# DOut.net
KiCad netlist of a schematic drawn in Altium Designer
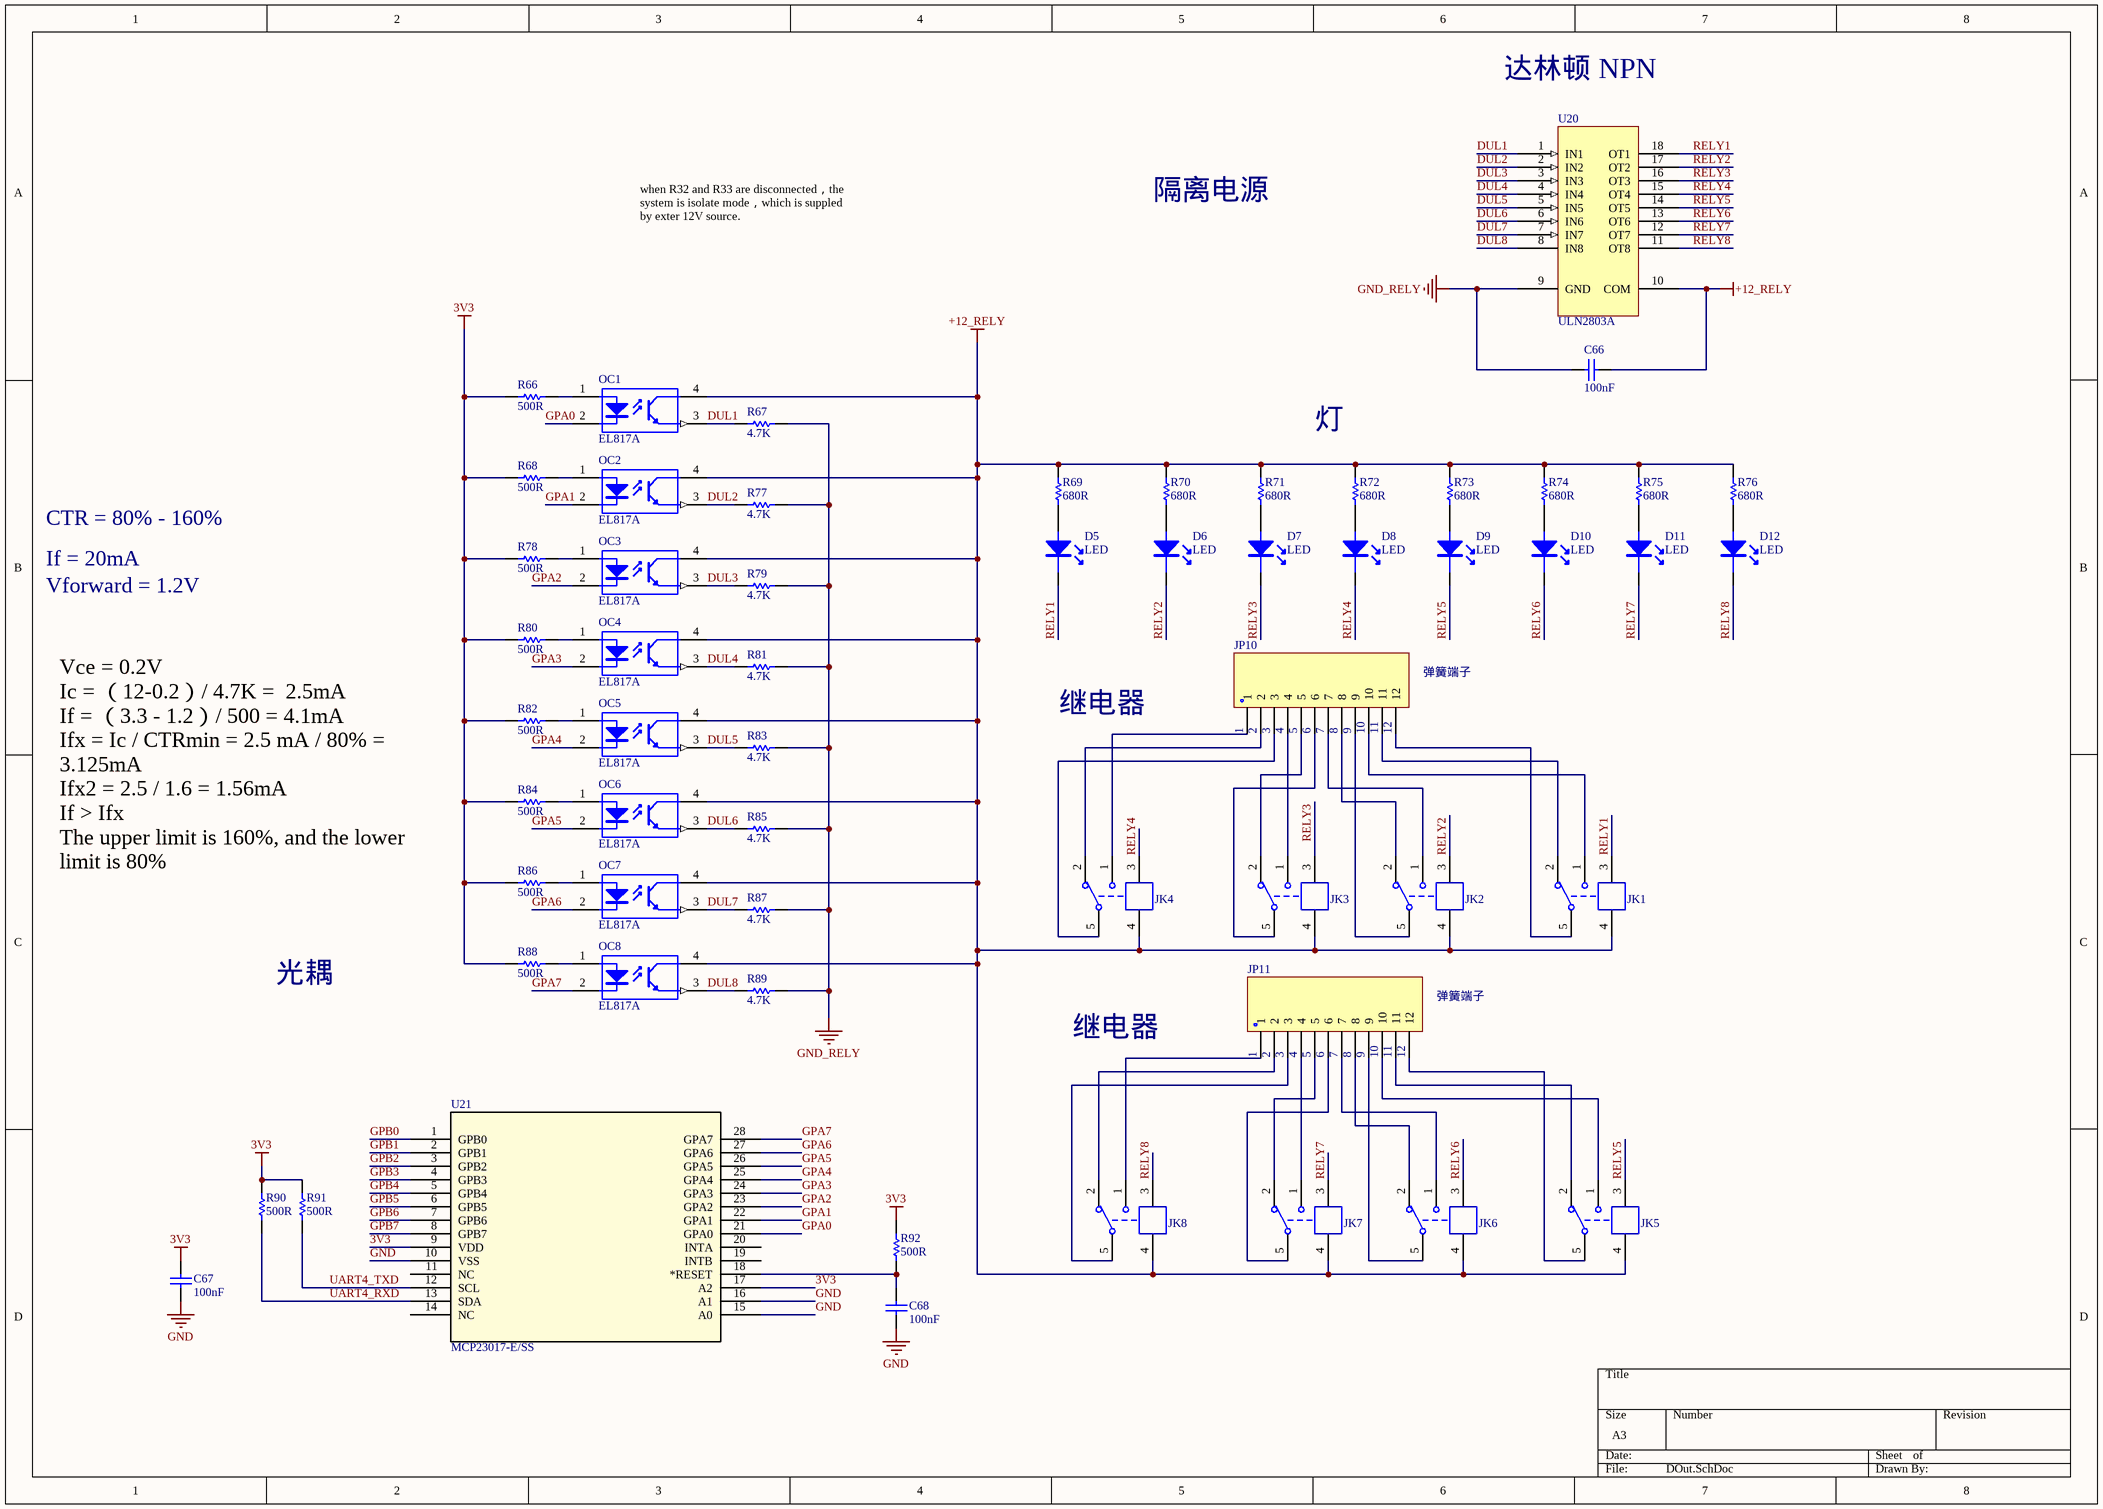
[diagram p0: DOut.SchDoc]

(export (version "E")
  (design (tool "Eeschema 10.0.6"))
  (components
    (comp (ref "C66")
      (value "100nF")
      (footprint "0603C")
      (description "Capacitor")
      (fields (field (name "PUBLISHER") "Altium Limited"))
      (libsource (lib "LJTV1.0") (part "CAP"))
    )
    (comp (ref "C67")
      (value "100nF")
      (footprint "0603C")
      (description "Capacitor")
      (fields (field (name "PUBLISHER") "Altium Limited"))
      (libsource (lib "WarShip_ExtraBoard") (part "CAP"))
    )
    (comp (ref "C68")
      (value "100nF")
      (footprint "0603C")
      (description "Capacitor")
      (fields (field (name "PUBLISHER") "Altium Limited"))
      (libsource (lib "WarShip_ExtraBoard") (part "CAP"))
    )
    (comp (ref "D5")
      (value "LED")
      (footprint "LED-0603G")
      (description "LED 发光二极管")
      (libsource (lib "LJTV1.0") (part "LED"))
    )
    (comp (ref "D6")
      (value "LED")
      (footprint "LED-0603G")
      (description "LED 发光二极管")
      (libsource (lib "LJTV1.0") (part "LED"))
    )
    (comp (ref "D7")
      (value "LED")
      (footprint "LED-0603G")
      (description "LED 发光二极管")
      (libsource (lib "LJTV1.0") (part "LED"))
    )
    (comp (ref "D8")
      (value "LED")
      (footprint "LED-0603G")
      (description "LED 发光二极管")
      (libsource (lib "LJTV1.0") (part "LED"))
    )
    (comp (ref "D9")
      (value "LED")
      (footprint "LED-0603G")
      (description "LED 发光二极管")
      (libsource (lib "LJTV1.0") (part "LED"))
    )
    (comp (ref "D10")
      (value "LED")
      (footprint "LED-0603G")
      (description "LED 发光二极管")
      (libsource (lib "LJTV1.0") (part "LED"))
    )
    (comp (ref "D11")
      (value "LED")
      (footprint "LED-0603G")
      (description "LED 发光二极管")
      (libsource (lib "LJTV1.0") (part "LED"))
    )
    (comp (ref "D12")
      (value "LED")
      (footprint "LED-0603G")
      (description "LED 发光二极管")
      (libsource (lib "LJTV1.0") (part "LED"))
    )
    (comp (ref "JK1")
      (value "JS-12-K")
      (footprint "JS-12-K")
      (description "12V一组转换")
      (libsource (lib "Extra_Board_Mini") (part "JS-12-K"))
    )
    (comp (ref "JK2")
      (value "JS-12-K")
      (footprint "JS-12-K")
      (description "12V一组转换")
      (libsource (lib "Extra_Board_Mini") (part "JS-12-K"))
    )
    (comp (ref "JK3")
      (value "JS-12-K")
      (footprint "JS-12-K")
      (description "12V一组转换")
      (libsource (lib "Extra_Board_Mini") (part "JS-12-K"))
    )
    (comp (ref "JK4")
      (value "JS-12-K")
      (footprint "JS-12-K")
      (description "12V一组转换")
      (libsource (lib "Extra_Board_Mini") (part "JS-12-K"))
    )
    (comp (ref "JK5")
      (value "JS-12-K")
      (footprint "JS-12-K")
      (description "12V一组转换")
      (libsource (lib "Extra_Board_Mini") (part "JS-12-K"))
    )
    (comp (ref "JK6")
      (value "JS-12-K")
      (footprint "JS-12-K")
      (description "12V一组转换")
      (libsource (lib "Extra_Board_Mini") (part "JS-12-K"))
    )
    (comp (ref "JK7")
      (value "JS-12-K")
      (footprint "JS-12-K")
      (description "12V一组转换")
      (libsource (lib "Extra_Board_Mini") (part "JS-12-K"))
    )
    (comp (ref "JK8")
      (value "JS-12-K")
      (footprint "JS-12-K")
      (description "12V一组转换")
      (libsource (lib "Extra_Board_Mini") (part "JS-12-K"))
    )
    (comp (ref "JP10")
      (value "弹簧端子")
      (footprint "DB142V-5.08-12P")
      (libsource (lib "Extra_Board_Mini") (part "DB142V-5.08-12P"))
    )
    (comp (ref "JP11")
      (value "弹簧端子")
      (footprint "DB142V-5.08-12P")
      (libsource (lib "Extra_Board_Mini") (part "DB142V-5.08-12P"))
    )
    (comp (ref "OC1")
      (value "EL817A")
      (footprint "SMD_PC817")
      (description "线性光耦")
      (libsource (lib "LJTV1.0") (part "EL357N"))
    )
    (comp (ref "OC2")
      (value "EL817A")
      (footprint "SMD_PC817")
      (description "线性光耦")
      (libsource (lib "LJTV1.0") (part "EL357N"))
    )
    (comp (ref "OC3")
      (value "EL817A")
      (footprint "SMD_PC817")
      (description "线性光耦")
      (libsource (lib "LJTV1.0") (part "EL357N"))
    )
    (comp (ref "OC4")
      (value "EL817A")
      (footprint "SMD_PC817")
      (description "线性光耦")
      (libsource (lib "LJTV1.0") (part "EL357N"))
    )
    (comp (ref "OC5")
      (value "EL817A")
      (footprint "SMD_PC817")
      (description "线性光耦")
      (libsource (lib "LJTV1.0") (part "EL357N"))
    )
    (comp (ref "OC6")
      (value "EL817A")
      (footprint "SMD_PC817")
      (description "线性光耦")
      (libsource (lib "LJTV1.0") (part "EL357N"))
    )
    (comp (ref "OC7")
      (value "EL817A")
      (footprint "SMD_PC817")
      (description "线性光耦")
      (libsource (lib "LJTV1.0") (part "EL357N"))
    )
    (comp (ref "OC8")
      (value "EL817A")
      (footprint "SMD_PC817")
      (description "线性光耦")
      (libsource (lib "LJTV1.0") (part "EL357N"))
    )
    (comp (ref "R66")
      (value "500R")
      (footprint "0603r")
      (description "Resistor")
      (fields (field (name "PUBLISHER") "Altium Limited"))
      (libsource (lib "LJTV1.0") (part "RES"))
    )
    (comp (ref "R67")
      (value "4.7K")
      (footprint "0603R")
      (description "Resistor")
      (fields (field (name "PUBLISHER") "Altium Limited"))
      (libsource (lib "LJTV1.0") (part "RES"))
    )
    (comp (ref "R68")
      (value "500R")
      (footprint "0603r")
      (description "Resistor")
      (fields (field (name "PUBLISHER") "Altium Limited"))
      (libsource (lib "LJTV1.0") (part "RES"))
    )
    (comp (ref "R69")
      (value "680R")
      (footprint "0603r")
      (description "Resistor")
      (fields (field (name "PUBLISHER") "Altium Limited"))
      (libsource (lib "LJTV1.0") (part "RES"))
    )
    (comp (ref "R70")
      (value "680R")
      (footprint "0603r")
      (description "Resistor")
      (fields (field (name "PUBLISHER") "Altium Limited"))
      (libsource (lib "LJTV1.0") (part "RES"))
    )
    (comp (ref "R71")
      (value "680R")
      (footprint "0603r")
      (description "Resistor")
      (fields (field (name "PUBLISHER") "Altium Limited"))
      (libsource (lib "LJTV1.0") (part "RES"))
    )
    (comp (ref "R72")
      (value "680R")
      (footprint "0603r")
      (description "Resistor")
      (fields (field (name "PUBLISHER") "Altium Limited"))
      (libsource (lib "LJTV1.0") (part "RES"))
    )
    (comp (ref "R73")
      (value "680R")
      (footprint "0603r")
      (description "Resistor")
      (fields (field (name "PUBLISHER") "Altium Limited"))
      (libsource (lib "LJTV1.0") (part "RES"))
    )
    (comp (ref "R74")
      (value "680R")
      (footprint "0603r")
      (description "Resistor")
      (fields (field (name "PUBLISHER") "Altium Limited"))
      (libsource (lib "LJTV1.0") (part "RES"))
    )
    (comp (ref "R75")
      (value "680R")
      (footprint "0603r")
      (description "Resistor")
      (fields (field (name "PUBLISHER") "Altium Limited"))
      (libsource (lib "LJTV1.0") (part "RES"))
    )
    (comp (ref "R76")
      (value "680R")
      (footprint "0603r")
      (description "Resistor")
      (fields (field (name "PUBLISHER") "Altium Limited"))
      (libsource (lib "LJTV1.0") (part "RES"))
    )
    (comp (ref "R77")
      (value "4.7K")
      (footprint "0603R")
      (description "Resistor")
      (fields (field (name "PUBLISHER") "Altium Limited"))
      (libsource (lib "LJTV1.0") (part "RES"))
    )
    (comp (ref "R78")
      (value "500R")
      (footprint "0603r")
      (description "Resistor")
      (fields (field (name "PUBLISHER") "Altium Limited"))
      (libsource (lib "LJTV1.0") (part "RES"))
    )
    (comp (ref "R79")
      (value "4.7K")
      (footprint "0603R")
      (description "Resistor")
      (fields (field (name "PUBLISHER") "Altium Limited"))
      (libsource (lib "LJTV1.0") (part "RES"))
    )
    (comp (ref "R80")
      (value "500R")
      (footprint "0603r")
      (description "Resistor")
      (fields (field (name "PUBLISHER") "Altium Limited"))
      (libsource (lib "LJTV1.0") (part "RES"))
    )
    (comp (ref "R81")
      (value "4.7K")
      (footprint "0603R")
      (description "Resistor")
      (fields (field (name "PUBLISHER") "Altium Limited"))
      (libsource (lib "LJTV1.0") (part "RES"))
    )
    (comp (ref "R82")
      (value "500R")
      (footprint "0603r")
      (description "Resistor")
      (fields (field (name "PUBLISHER") "Altium Limited"))
      (libsource (lib "LJTV1.0") (part "RES"))
    )
    (comp (ref "R83")
      (value "4.7K")
      (footprint "0603R")
      (description "Resistor")
      (fields (field (name "PUBLISHER") "Altium Limited"))
      (libsource (lib "LJTV1.0") (part "RES"))
    )
    (comp (ref "R84")
      (value "500R")
      (footprint "0603r")
      (description "Resistor")
      (fields (field (name "PUBLISHER") "Altium Limited"))
      (libsource (lib "LJTV1.0") (part "RES"))
    )
    (comp (ref "R85")
      (value "4.7K")
      (footprint "0603R")
      (description "Resistor")
      (fields (field (name "PUBLISHER") "Altium Limited"))
      (libsource (lib "LJTV1.0") (part "RES"))
    )
    (comp (ref "R86")
      (value "500R")
      (footprint "0603r")
      (description "Resistor")
      (fields (field (name "PUBLISHER") "Altium Limited"))
      (libsource (lib "LJTV1.0") (part "RES"))
    )
    (comp (ref "R87")
      (value "4.7K")
      (footprint "0603R")
      (description "Resistor")
      (fields (field (name "PUBLISHER") "Altium Limited"))
      (libsource (lib "LJTV1.0") (part "RES"))
    )
    (comp (ref "R88")
      (value "500R")
      (footprint "0603r")
      (description "Resistor")
      (fields (field (name "PUBLISHER") "Altium Limited"))
      (libsource (lib "LJTV1.0") (part "RES"))
    )
    (comp (ref "R89")
      (value "4.7K")
      (footprint "0603R")
      (description "Resistor")
      (fields (field (name "PUBLISHER") "Altium Limited"))
      (libsource (lib "LJTV1.0") (part "RES"))
    )
    (comp (ref "R90")
      (value "500R")
      (footprint "0603r")
      (description "Resistor")
      (fields (field (name "PUBLISHER") "Altium Limited"))
      (libsource (lib "WarShip_ExtraBoard") (part "RES"))
    )
    (comp (ref "R91")
      (value "500R")
      (footprint "0603r")
      (description "Resistor")
      (fields (field (name "PUBLISHER") "Altium Limited"))
      (libsource (lib "WarShip_ExtraBoard") (part "RES"))
    )
    (comp (ref "R92")
      (value "500R")
      (footprint "0603r")
      (description "Resistor")
      (fields (field (name "PUBLISHER") "Altium Limited"))
      (libsource (lib "WarShip_ExtraBoard") (part "RES"))
    )
    (comp (ref "U20")
      (value "ULN2803A")
      (footprint "SOP18 - 300mil")
      (description "8 channels Darlington")
      (libsource (lib "LJTV1.0") (part "ULN2803A"))
    )
    (comp (ref "U21")
      (value "MCP23017-E/SS")
      (footprint "SSOP28_MC_MCH")
      (description "No Description Available")
      (fields (field (name "COPYRIGHT") "Copyright (C) 2021 Ultra Librarian. All rights reserved."))
      (libsource (lib "MCP23017-E&slash_SS") (part "MCP23017-E/SS"))
    )
  )
  (nets
    (net (code "1") (name "+12_RELY") (class "Default")
      (node (ref "C66") (pin "2") (pinfunction "2_2") (pintype "passive"))
      (node (ref "JK1") (pin "4") (pinfunction "4_4") (pintype "passive"))
      (node (ref "JK2") (pin "4") (pinfunction "4_4") (pintype "passive"))
      (node (ref "JK3") (pin "4") (pinfunction "4_4") (pintype "passive"))
      (node (ref "JK4") (pin "4") (pinfunction "4_4") (pintype "passive"))
      (node (ref "JK5") (pin "4") (pinfunction "4_4") (pintype "passive"))
      (node (ref "JK6") (pin "4") (pinfunction "4_4") (pintype "passive"))
      (node (ref "JK7") (pin "4") (pinfunction "4_4") (pintype "passive"))
      (node (ref "JK8") (pin "4") (pinfunction "4_4") (pintype "passive"))
      (node (ref "OC1") (pin "4") (pinfunction "C_4") (pintype "passive"))
      (node (ref "OC2") (pin "4") (pinfunction "C_4") (pintype "passive"))
      (node (ref "OC3") (pin "4") (pinfunction "C_4") (pintype "passive"))
      (node (ref "OC4") (pin "4") (pinfunction "C_4") (pintype "passive"))
      (node (ref "OC5") (pin "4") (pinfunction "C_4") (pintype "passive"))
      (node (ref "OC6") (pin "4") (pinfunction "C_4") (pintype "passive"))
      (node (ref "OC7") (pin "4") (pinfunction "C_4") (pintype "passive"))
      (node (ref "OC8") (pin "4") (pinfunction "C_4") (pintype "passive"))
      (node (ref "R69") (pin "1") (pinfunction "1_1") (pintype "passive"))
      (node (ref "R70") (pin "1") (pinfunction "1_1") (pintype "passive"))
      (node (ref "R71") (pin "1") (pinfunction "1_1") (pintype "passive"))
      (node (ref "R72") (pin "1") (pinfunction "1_1") (pintype "passive"))
      (node (ref "R73") (pin "1") (pinfunction "1_1") (pintype "passive"))
      (node (ref "R74") (pin "1") (pinfunction "1_1") (pintype "passive"))
      (node (ref "R75") (pin "1") (pinfunction "1_1") (pintype "passive"))
      (node (ref "R76") (pin "1") (pinfunction "1_1") (pintype "passive"))
      (node (ref "U20") (pin "10") (pinfunction "COM_10") (pintype "power_in"))
    )
    (net (code "2") (name "/DUL1") (class "Default")
      (node (ref "OC1") (pin "3") (pinfunction "E_3") (pintype "output"))
      (node (ref "R67") (pin "1") (pinfunction "1_1") (pintype "passive"))
      (node (ref "U20") (pin "1") (pinfunction "IN1_1") (pintype "input"))
    )
    (net (code "3") (name "/DUL2") (class "Default")
      (node (ref "OC2") (pin "3") (pinfunction "E_3") (pintype "output"))
      (node (ref "R77") (pin "1") (pinfunction "1_1") (pintype "passive"))
      (node (ref "U20") (pin "2") (pinfunction "IN2_2") (pintype "input"))
    )
    (net (code "4") (name "/DUL3") (class "Default")
      (node (ref "OC3") (pin "3") (pinfunction "E_3") (pintype "output"))
      (node (ref "R79") (pin "1") (pinfunction "1_1") (pintype "passive"))
      (node (ref "U20") (pin "3") (pinfunction "IN3_3") (pintype "input"))
    )
    (net (code "5") (name "/DUL4") (class "Default")
      (node (ref "OC4") (pin "3") (pinfunction "E_3") (pintype "output"))
      (node (ref "R81") (pin "1") (pinfunction "1_1") (pintype "passive"))
      (node (ref "U20") (pin "4") (pinfunction "IN4_4") (pintype "input"))
    )
    (net (code "6") (name "/DUL5") (class "Default")
      (node (ref "OC5") (pin "3") (pinfunction "E_3") (pintype "output"))
      (node (ref "R83") (pin "1") (pinfunction "1_1") (pintype "passive"))
      (node (ref "U20") (pin "5") (pinfunction "IN5_5") (pintype "input"))
    )
    (net (code "7") (name "/DUL6") (class "Default")
      (node (ref "OC6") (pin "3") (pinfunction "E_3") (pintype "output"))
      (node (ref "R85") (pin "1") (pinfunction "1_1") (pintype "passive"))
      (node (ref "U20") (pin "6") (pinfunction "IN6_6") (pintype "input"))
    )
    (net (code "8") (name "/DUL7") (class "Default")
      (node (ref "OC7") (pin "3") (pinfunction "E_3") (pintype "output"))
      (node (ref "R87") (pin "1") (pinfunction "1_1") (pintype "passive"))
      (node (ref "U20") (pin "7") (pinfunction "IN7_7") (pintype "input"))
    )
    (net (code "9") (name "/DUL8") (class "Default")
      (node (ref "OC8") (pin "3") (pinfunction "E_3") (pintype "output"))
      (node (ref "R89") (pin "1") (pinfunction "1_1") (pintype "passive"))
      (node (ref "U20") (pin "8") (pinfunction "IN8_8") (pintype "passive"))
    )
    (net (code "10") (name "/GPA0") (class "Default")
      (node (ref "OC1") (pin "2") (pinfunction "K_2") (pintype "passive"))
      (node (ref "U21") (pin "21") (pinfunction "GPA0_21") (pintype "passive"))
    )
    (net (code "11") (name "/GPA1") (class "Default")
      (node (ref "OC2") (pin "2") (pinfunction "K_2") (pintype "passive"))
      (node (ref "U21") (pin "22") (pinfunction "GPA1_22") (pintype "passive"))
    )
    (net (code "12") (name "/GPA2") (class "Default")
      (node (ref "OC3") (pin "2") (pinfunction "K_2") (pintype "passive"))
      (node (ref "U21") (pin "23") (pinfunction "GPA2_23") (pintype "passive"))
    )
    (net (code "13") (name "/GPA3") (class "Default")
      (node (ref "OC4") (pin "2") (pinfunction "K_2") (pintype "passive"))
      (node (ref "U21") (pin "24") (pinfunction "GPA3_24") (pintype "passive"))
    )
    (net (code "14") (name "/GPA4") (class "Default")
      (node (ref "OC5") (pin "2") (pinfunction "K_2") (pintype "passive"))
      (node (ref "U21") (pin "25") (pinfunction "GPA4_25") (pintype "passive"))
    )
    (net (code "15") (name "/GPA5") (class "Default")
      (node (ref "OC6") (pin "2") (pinfunction "K_2") (pintype "passive"))
      (node (ref "U21") (pin "26") (pinfunction "GPA5_26") (pintype "passive"))
    )
    (net (code "16") (name "/GPA6") (class "Default")
      (node (ref "OC7") (pin "2") (pinfunction "K_2") (pintype "passive"))
      (node (ref "U21") (pin "27") (pinfunction "GPA6_27") (pintype "passive"))
    )
    (net (code "17") (name "/GPA7") (class "Default")
      (node (ref "OC8") (pin "2") (pinfunction "K_2") (pintype "passive"))
      (node (ref "U21") (pin "28") (pinfunction "GPA7_28") (pintype "passive"))
    )
    (net (code "18") (name "/GPB0") (class "Default")
      (node (ref "U21") (pin "1") (pinfunction "GPB0_1") (pintype "passive"))
    )
    (net (code "19") (name "/GPB1") (class "Default")
      (node (ref "U21") (pin "2") (pinfunction "GPB1_2") (pintype "passive"))
    )
    (net (code "20") (name "/GPB2") (class "Default")
      (node (ref "U21") (pin "3") (pinfunction "GPB2_3") (pintype "passive"))
    )
    (net (code "21") (name "/GPB3") (class "Default")
      (node (ref "U21") (pin "4") (pinfunction "GPB3_4") (pintype "passive"))
    )
    (net (code "22") (name "/GPB4") (class "Default")
      (node (ref "U21") (pin "5") (pinfunction "GPB4_5") (pintype "passive"))
    )
    (net (code "23") (name "/GPB5") (class "Default")
      (node (ref "U21") (pin "6") (pinfunction "GPB5_6") (pintype "passive"))
    )
    (net (code "24") (name "/GPB6") (class "Default")
      (node (ref "U21") (pin "7") (pinfunction "GPB6_7") (pintype "passive"))
    )
    (net (code "25") (name "/GPB7") (class "Default")
      (node (ref "U21") (pin "8") (pinfunction "GPB7_8") (pintype "passive"))
    )
    (net (code "26") (name "/RELY1") (class "Default")
      (node (ref "D5") (pin "2") (pinfunction "K_2") (pintype "passive"))
      (node (ref "JK1") (pin "3") (pinfunction "3_3") (pintype "passive"))
      (node (ref "U20") (pin "18") (pinfunction "OT1_18") (pintype "passive"))
    )
    (net (code "27") (name "/RELY2") (class "Default")
      (node (ref "D6") (pin "2") (pinfunction "K_2") (pintype "passive"))
      (node (ref "JK2") (pin "3") (pinfunction "3_3") (pintype "passive"))
      (node (ref "U20") (pin "17") (pinfunction "OT2_17") (pintype "passive"))
    )
    (net (code "28") (name "/RELY3") (class "Default")
      (node (ref "D7") (pin "2") (pinfunction "K_2") (pintype "passive"))
      (node (ref "JK3") (pin "3") (pinfunction "3_3") (pintype "passive"))
      (node (ref "U20") (pin "16") (pinfunction "OT3_16") (pintype "passive"))
    )
    (net (code "29") (name "/RELY4") (class "Default")
      (node (ref "D8") (pin "2") (pinfunction "K_2") (pintype "passive"))
      (node (ref "JK4") (pin "3") (pinfunction "3_3") (pintype "passive"))
      (node (ref "U20") (pin "15") (pinfunction "OT4_15") (pintype "passive"))
    )
    (net (code "30") (name "/RELY5") (class "Default")
      (node (ref "D9") (pin "2") (pinfunction "K_2") (pintype "passive"))
      (node (ref "JK5") (pin "3") (pinfunction "3_3") (pintype "passive"))
      (node (ref "U20") (pin "14") (pinfunction "OT5_14") (pintype "passive"))
    )
    (net (code "31") (name "/RELY6") (class "Default")
      (node (ref "D10") (pin "2") (pinfunction "K_2") (pintype "passive"))
      (node (ref "JK6") (pin "3") (pinfunction "3_3") (pintype "passive"))
      (node (ref "U20") (pin "13") (pinfunction "OT6_13") (pintype "passive"))
    )
    (net (code "32") (name "/RELY7") (class "Default")
      (node (ref "D11") (pin "2") (pinfunction "K_2") (pintype "passive"))
      (node (ref "JK7") (pin "3") (pinfunction "3_3") (pintype "passive"))
      (node (ref "U20") (pin "12") (pinfunction "OT7_12") (pintype "passive"))
    )
    (net (code "33") (name "/RELY8") (class "Default")
      (node (ref "D12") (pin "2") (pinfunction "K_2") (pintype "passive"))
      (node (ref "JK8") (pin "3") (pinfunction "3_3") (pintype "passive"))
      (node (ref "U20") (pin "11") (pinfunction "OT8_11") (pintype "passive"))
    )
    (net (code "34") (name "/UART4_RXD") (class "Default")
      (node (ref "R90") (pin "1") (pinfunction "1_1") (pintype "passive"))
      (node (ref "U21") (pin "13") (pinfunction "SDA_13") (pintype "passive"))
    )
    (net (code "35") (name "/UART4_TXD") (class "Default")
      (node (ref "R91") (pin "1") (pinfunction "1_1") (pintype "passive"))
      (node (ref "U21") (pin "12") (pinfunction "SCL_12") (pintype "passive"))
    )
    (net (code "36") (name "3V3") (class "Default")
      (node (ref "C67") (pin "2") (pinfunction "2_2") (pintype "passive"))
      (node (ref "R66") (pin "2") (pinfunction "2_2") (pintype "passive"))
      (node (ref "R68") (pin "2") (pinfunction "2_2") (pintype "passive"))
      (node (ref "R78") (pin "2") (pinfunction "2_2") (pintype "passive"))
      (node (ref "R80") (pin "2") (pinfunction "2_2") (pintype "passive"))
      (node (ref "R82") (pin "2") (pinfunction "2_2") (pintype "passive"))
      (node (ref "R84") (pin "2") (pinfunction "2_2") (pintype "passive"))
      (node (ref "R86") (pin "2") (pinfunction "2_2") (pintype "passive"))
      (node (ref "R88") (pin "2") (pinfunction "2_2") (pintype "passive"))
      (node (ref "R90") (pin "2") (pinfunction "2_2") (pintype "passive"))
      (node (ref "R91") (pin "2") (pinfunction "2_2") (pintype "passive"))
      (node (ref "R92") (pin "2") (pinfunction "2_2") (pintype "passive"))
      (node (ref "U21") (pin "17") (pinfunction "A2_17") (pintype "passive"))
      (node (ref "U21") (pin "9") (pinfunction "VDD_9") (pintype "passive"))
    )
    (net (code "37") (name "GND") (class "Default")
      (node (ref "C67") (pin "1") (pinfunction "1_1") (pintype "passive"))
      (node (ref "C68") (pin "1") (pinfunction "1_1") (pintype "passive"))
      (node (ref "U21") (pin "10") (pinfunction "VSS_10") (pintype "passive"))
      (node (ref "U21") (pin "15") (pinfunction "A0_15") (pintype "passive"))
      (node (ref "U21") (pin "16") (pinfunction "A1_16") (pintype "passive"))
    )
    (net (code "38") (name "GND_RELY") (class "Default")
      (node (ref "C66") (pin "1") (pinfunction "1_1") (pintype "passive"))
      (node (ref "R67") (pin "2") (pinfunction "2_2") (pintype "passive"))
      (node (ref "R77") (pin "2") (pinfunction "2_2") (pintype "passive"))
      (node (ref "R79") (pin "2") (pinfunction "2_2") (pintype "passive"))
      (node (ref "R81") (pin "2") (pinfunction "2_2") (pintype "passive"))
      (node (ref "R83") (pin "2") (pinfunction "2_2") (pintype "passive"))
      (node (ref "R85") (pin "2") (pinfunction "2_2") (pintype "passive"))
      (node (ref "R87") (pin "2") (pinfunction "2_2") (pintype "passive"))
      (node (ref "R89") (pin "2") (pinfunction "2_2") (pintype "passive"))
      (node (ref "U20") (pin "9") (pinfunction "GND_9") (pintype "power_in"))
    )
    (net (code "39") (name "Net-(D5-A)") (class "Default")
      (node (ref "D5") (pin "1") (pinfunction "A_1") (pintype "passive"))
      (node (ref "R69") (pin "2") (pinfunction "2_2") (pintype "passive"))
    )
    (net (code "40") (name "Net-(D6-A)") (class "Default")
      (node (ref "D6") (pin "1") (pinfunction "A_1") (pintype "passive"))
      (node (ref "R70") (pin "2") (pinfunction "2_2") (pintype "passive"))
    )
    (net (code "41") (name "Net-(D7-A)") (class "Default")
      (node (ref "D7") (pin "1") (pinfunction "A_1") (pintype "passive"))
      (node (ref "R71") (pin "2") (pinfunction "2_2") (pintype "passive"))
    )
    (net (code "42") (name "Net-(D8-A)") (class "Default")
      (node (ref "D8") (pin "1") (pinfunction "A_1") (pintype "passive"))
      (node (ref "R72") (pin "2") (pinfunction "2_2") (pintype "passive"))
    )
    (net (code "43") (name "Net-(D9-A)") (class "Default")
      (node (ref "D9") (pin "1") (pinfunction "A_1") (pintype "passive"))
      (node (ref "R73") (pin "2") (pinfunction "2_2") (pintype "passive"))
    )
    (net (code "44") (name "Net-(D10-A)") (class "Default")
      (node (ref "D10") (pin "1") (pinfunction "A_1") (pintype "passive"))
      (node (ref "R74") (pin "2") (pinfunction "2_2") (pintype "passive"))
    )
    (net (code "45") (name "Net-(D11-A)") (class "Default")
      (node (ref "D11") (pin "1") (pinfunction "A_1") (pintype "passive"))
      (node (ref "R75") (pin "2") (pinfunction "2_2") (pintype "passive"))
    )
    (net (code "46") (name "Net-(D12-A)") (class "Default")
      (node (ref "D12") (pin "1") (pinfunction "A_1") (pintype "passive"))
      (node (ref "R76") (pin "2") (pinfunction "2_2") (pintype "passive"))
    )
    (net (code "47") (name "Net-(JK1-Pad1)") (class "Default")
      (node (ref "JK1") (pin "1") (pinfunction "1_1") (pintype "passive"))
      (node (ref "JP10") (pin "10") (pinfunction "10_10") (pintype "passive"))
    )
    (net (code "48") (name "Net-(JK1-Pad2)") (class "Default")
      (node (ref "JK1") (pin "2") (pinfunction "2_2") (pintype "passive"))
      (node (ref "JP10") (pin "11") (pinfunction "11_11") (pintype "passive"))
    )
    (net (code "49") (name "Net-(JK1-Pad5)") (class "Default")
      (node (ref "JK1") (pin "5") (pinfunction "5_5") (pintype "passive"))
      (node (ref "JP10") (pin "12") (pinfunction "12_12") (pintype "passive"))
    )
    (net (code "50") (name "Net-(JK2-Pad1)") (class "Default")
      (node (ref "JK2") (pin "1") (pinfunction "1_1") (pintype "passive"))
      (node (ref "JP10") (pin "7") (pinfunction "7_7") (pintype "passive"))
    )
    (net (code "51") (name "Net-(JK2-Pad2)") (class "Default")
      (node (ref "JK2") (pin "2") (pinfunction "2_2") (pintype "passive"))
      (node (ref "JP10") (pin "8") (pinfunction "8_8") (pintype "passive"))
    )
    (net (code "52") (name "Net-(JK2-Pad5)") (class "Default")
      (node (ref "JK2") (pin "5") (pinfunction "5_5") (pintype "passive"))
      (node (ref "JP10") (pin "9") (pinfunction "9_9") (pintype "passive"))
    )
    (net (code "53") (name "Net-(JK3-Pad1)") (class "Default")
      (node (ref "JK3") (pin "1") (pinfunction "1_1") (pintype "passive"))
      (node (ref "JP10") (pin "4") (pinfunction "4_4") (pintype "passive"))
    )
    (net (code "54") (name "Net-(JK3-Pad2)") (class "Default")
      (node (ref "JK3") (pin "2") (pinfunction "2_2") (pintype "passive"))
      (node (ref "JP10") (pin "5") (pinfunction "5_5") (pintype "passive"))
    )
    (net (code "55") (name "Net-(JK3-Pad5)") (class "Default")
      (node (ref "JK3") (pin "5") (pinfunction "5_5") (pintype "passive"))
      (node (ref "JP10") (pin "6") (pinfunction "6_6") (pintype "passive"))
    )
    (net (code "56") (name "Net-(JK4-Pad1)") (class "Default")
      (node (ref "JK4") (pin "1") (pinfunction "1_1") (pintype "passive"))
      (node (ref "JP10") (pin "1") (pinfunction "1_1") (pintype "passive"))
    )
    (net (code "57") (name "Net-(JK4-Pad2)") (class "Default")
      (node (ref "JK4") (pin "2") (pinfunction "2_2") (pintype "passive"))
      (node (ref "JP10") (pin "2") (pinfunction "2_2") (pintype "passive"))
    )
    (net (code "58") (name "Net-(JK4-Pad5)") (class "Default")
      (node (ref "JK4") (pin "5") (pinfunction "5_5") (pintype "passive"))
      (node (ref "JP10") (pin "3") (pinfunction "3_3") (pintype "passive"))
    )
    (net (code "59") (name "Net-(JK5-Pad1)") (class "Default")
      (node (ref "JK5") (pin "1") (pinfunction "1_1") (pintype "passive"))
      (node (ref "JP11") (pin "10") (pinfunction "10_10") (pintype "passive"))
    )
    (net (code "60") (name "Net-(JK5-Pad2)") (class "Default")
      (node (ref "JK5") (pin "2") (pinfunction "2_2") (pintype "passive"))
      (node (ref "JP11") (pin "11") (pinfunction "11_11") (pintype "passive"))
    )
    (net (code "61") (name "Net-(JK5-Pad5)") (class "Default")
      (node (ref "JK5") (pin "5") (pinfunction "5_5") (pintype "passive"))
      (node (ref "JP11") (pin "12") (pinfunction "12_12") (pintype "passive"))
    )
    (net (code "62") (name "Net-(JK6-Pad1)") (class "Default")
      (node (ref "JK6") (pin "1") (pinfunction "1_1") (pintype "passive"))
      (node (ref "JP11") (pin "7") (pinfunction "7_7") (pintype "passive"))
    )
    (net (code "63") (name "Net-(JK6-Pad2)") (class "Default")
      (node (ref "JK6") (pin "2") (pinfunction "2_2") (pintype "passive"))
      (node (ref "JP11") (pin "8") (pinfunction "8_8") (pintype "passive"))
    )
    (net (code "64") (name "Net-(JK6-Pad5)") (class "Default")
      (node (ref "JK6") (pin "5") (pinfunction "5_5") (pintype "passive"))
      (node (ref "JP11") (pin "9") (pinfunction "9_9") (pintype "passive"))
    )
    (net (code "65") (name "Net-(JK7-Pad1)") (class "Default")
      (node (ref "JK7") (pin "1") (pinfunction "1_1") (pintype "passive"))
      (node (ref "JP11") (pin "4") (pinfunction "4_4") (pintype "passive"))
    )
    (net (code "66") (name "Net-(JK7-Pad2)") (class "Default")
      (node (ref "JK7") (pin "2") (pinfunction "2_2") (pintype "passive"))
      (node (ref "JP11") (pin "5") (pinfunction "5_5") (pintype "passive"))
    )
    (net (code "67") (name "Net-(JK7-Pad5)") (class "Default")
      (node (ref "JK7") (pin "5") (pinfunction "5_5") (pintype "passive"))
      (node (ref "JP11") (pin "6") (pinfunction "6_6") (pintype "passive"))
    )
    (net (code "68") (name "Net-(JK8-Pad1)") (class "Default")
      (node (ref "JK8") (pin "1") (pinfunction "1_1") (pintype "passive"))
      (node (ref "JP11") (pin "1") (pinfunction "1_1") (pintype "passive"))
    )
    (net (code "69") (name "Net-(JK8-Pad2)") (class "Default")
      (node (ref "JK8") (pin "2") (pinfunction "2_2") (pintype "passive"))
      (node (ref "JP11") (pin "2") (pinfunction "2_2") (pintype "passive"))
    )
    (net (code "70") (name "Net-(JK8-Pad5)") (class "Default")
      (node (ref "JK8") (pin "5") (pinfunction "5_5") (pintype "passive"))
      (node (ref "JP11") (pin "3") (pinfunction "3_3") (pintype "passive"))
    )
    (net (code "71") (name "Net-(OC1-A)") (class "Default")
      (node (ref "OC1") (pin "1") (pinfunction "A_1") (pintype "passive"))
      (node (ref "R66") (pin "1") (pinfunction "1_1") (pintype "passive"))
    )
    (net (code "72") (name "Net-(OC2-A)") (class "Default")
      (node (ref "OC2") (pin "1") (pinfunction "A_1") (pintype "passive"))
      (node (ref "R68") (pin "1") (pinfunction "1_1") (pintype "passive"))
    )
    (net (code "73") (name "Net-(OC3-A)") (class "Default")
      (node (ref "OC3") (pin "1") (pinfunction "A_1") (pintype "passive"))
      (node (ref "R78") (pin "1") (pinfunction "1_1") (pintype "passive"))
    )
    (net (code "74") (name "Net-(OC4-A)") (class "Default")
      (node (ref "OC4") (pin "1") (pinfunction "A_1") (pintype "passive"))
      (node (ref "R80") (pin "1") (pinfunction "1_1") (pintype "passive"))
    )
    (net (code "75") (name "Net-(OC5-A)") (class "Default")
      (node (ref "OC5") (pin "1") (pinfunction "A_1") (pintype "passive"))
      (node (ref "R82") (pin "1") (pinfunction "1_1") (pintype "passive"))
    )
    (net (code "76") (name "Net-(OC6-A)") (class "Default")
      (node (ref "OC6") (pin "1") (pinfunction "A_1") (pintype "passive"))
      (node (ref "R84") (pin "1") (pinfunction "1_1") (pintype "passive"))
    )
    (net (code "77") (name "Net-(OC7-A)") (class "Default")
      (node (ref "OC7") (pin "1") (pinfunction "A_1") (pintype "passive"))
      (node (ref "R86") (pin "1") (pinfunction "1_1") (pintype "passive"))
    )
    (net (code "78") (name "Net-(OC8-A)") (class "Default")
      (node (ref "OC8") (pin "1") (pinfunction "A_1") (pintype "passive"))
      (node (ref "R88") (pin "1") (pinfunction "1_1") (pintype "passive"))
    )
    (net (code "79") (name "Net-(U21-*RESET)") (class "Default")
      (node (ref "C68") (pin "2") (pinfunction "2_2") (pintype "passive"))
      (node (ref "R92") (pin "1") (pinfunction "1_1") (pintype "passive"))
      (node (ref "U21") (pin "18") (pinfunction "*RESET_18") (pintype "passive"))
    )
    (net (code "80") (name "unconnected-(U21-INTA-Pad20)") (class "Default")
      (node (ref "U21") (pin "20") (pinfunction "INTA_20") (pintype "passive"))
    )
    (net (code "81") (name "unconnected-(U21-INTB-Pad19)") (class "Default")
      (node (ref "U21") (pin "19") (pinfunction "INTB_19") (pintype "passive"))
    )
    (net (code "82") (name "unconnected-(U21-NC-Pad11)") (class "Default")
      (node (ref "U21") (pin "11") (pinfunction "NC_11") (pintype "passive"))
    )
    (net (code "83") (name "unconnected-(U21-NC-Pad14)") (class "Default")
      (node (ref "U21") (pin "14") (pinfunction "NC_14") (pintype "passive"))
    )
  )
)
